# relay_power_board.net
KiCad netlist of a schematic drawn in EAGLE
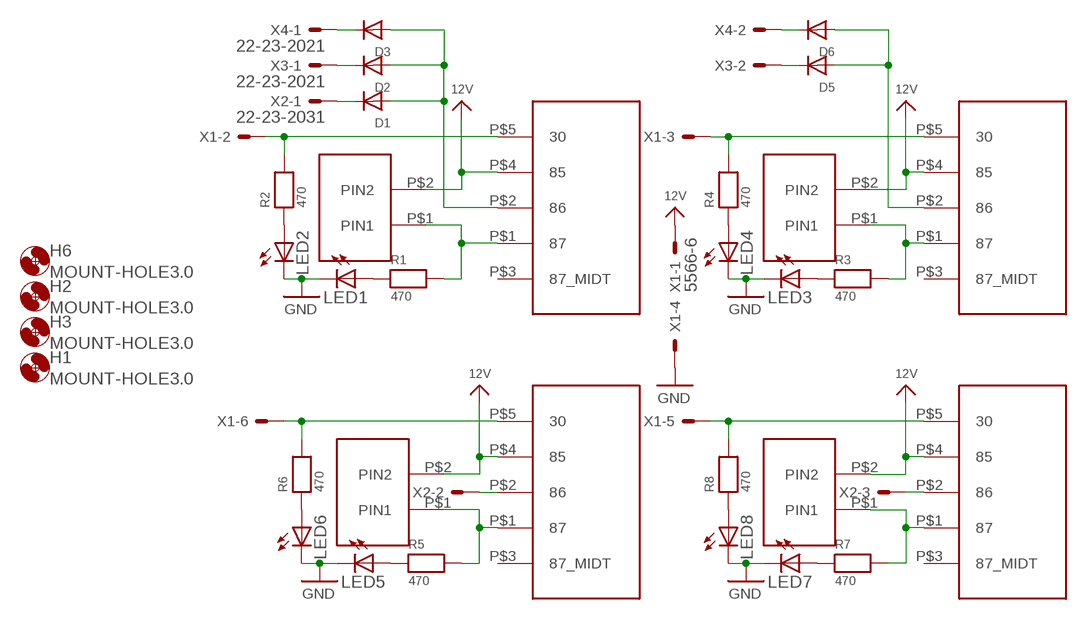
[diagram p0: schematic, sheet 1]

(export (version "E")
  (design (tool "Eeschema 10.0.6"))
  (components
    (comp (ref "D1")
      (value "DIODESMA")
      (footprint "eagle-import:SMADIODE")
      (libsource (lib "eagle-import") (part "DIODESMA"))
    )
    (comp (ref "D2")
      (value "DIODESMA")
      (footprint "eagle-import:SMADIODE")
      (libsource (lib "eagle-import") (part "DIODESMA"))
    )
    (comp (ref "D3")
      (value "DIODESMA")
      (footprint "eagle-import:SMADIODE")
      (libsource (lib "eagle-import") (part "DIODESMA"))
    )
    (comp (ref "D5")
      (value "DIODESMA")
      (footprint "eagle-import:SMADIODE")
      (libsource (lib "eagle-import") (part "DIODESMA"))
    )
    (comp (ref "D6")
      (value "DIODESMA")
      (footprint "eagle-import:SMADIODE")
      (libsource (lib "eagle-import") (part "DIODESMA"))
    )
    (comp (ref "H1")
      (value "MOUNT-HOLE3.0")
      (footprint "eagle-import:3,0")
      (libsource (lib "eagle-import") (part "MOUNT-HOLE3.0"))
    )
    (comp (ref "H2")
      (value "MOUNT-HOLE3.0")
      (footprint "eagle-import:3,0")
      (libsource (lib "eagle-import") (part "MOUNT-HOLE3.0"))
    )
    (comp (ref "H3")
      (value "MOUNT-HOLE3.0")
      (footprint "eagle-import:3,0")
      (libsource (lib "eagle-import") (part "MOUNT-HOLE3.0"))
    )
    (comp (ref "H6")
      (value "MOUNT-HOLE3.0")
      (footprint "eagle-import:3,0")
      (libsource (lib "eagle-import") (part "MOUNT-HOLE3.0"))
    )
    (comp (ref "LED1")
      (value "LEDCHIPLED_1206")
      (footprint "eagle-import:CHIPLED_1206")
      (libsource (lib "eagle-import") (part "LEDCHIPLED_1206"))
    )
    (comp (ref "LED2")
      (value "LEDCHIPLED_1206")
      (footprint "eagle-import:CHIPLED_1206")
      (libsource (lib "eagle-import") (part "LEDCHIPLED_1206"))
    )
    (comp (ref "LED3")
      (value "LEDCHIPLED_1206")
      (footprint "eagle-import:CHIPLED_1206")
      (libsource (lib "eagle-import") (part "LEDCHIPLED_1206"))
    )
    (comp (ref "LED4")
      (value "LEDCHIPLED_1206")
      (footprint "eagle-import:CHIPLED_1206")
      (libsource (lib "eagle-import") (part "LEDCHIPLED_1206"))
    )
    (comp (ref "LED5")
      (value "LEDCHIPLED_1206")
      (footprint "eagle-import:CHIPLED_1206")
      (libsource (lib "eagle-import") (part "LEDCHIPLED_1206"))
    )
    (comp (ref "LED6")
      (value "LEDCHIPLED_1206")
      (footprint "eagle-import:CHIPLED_1206")
      (libsource (lib "eagle-import") (part "LEDCHIPLED_1206"))
    )
    (comp (ref "LED7")
      (value "LEDCHIPLED_1206")
      (footprint "eagle-import:CHIPLED_1206")
      (libsource (lib "eagle-import") (part "LEDCHIPLED_1206"))
    )
    (comp (ref "LED8")
      (value "LEDCHIPLED_1206")
      (footprint "eagle-import:CHIPLED_1206")
      (libsource (lib "eagle-import") (part "LEDCHIPLED_1206"))
    )
    (comp (ref "R1")
      (value "470")
      (footprint "eagle-import:_0603")
      (libsource (lib "eagle-import") (part "RESISTOR_0603"))
    )
    (comp (ref "R2")
      (value "470")
      (footprint "eagle-import:_0603")
      (libsource (lib "eagle-import") (part "RESISTOR_0603"))
    )
    (comp (ref "R3")
      (value "470")
      (footprint "eagle-import:_0603")
      (libsource (lib "eagle-import") (part "RESISTOR_0603"))
    )
    (comp (ref "R4")
      (value "470")
      (footprint "eagle-import:_0603")
      (libsource (lib "eagle-import") (part "RESISTOR_0603"))
    )
    (comp (ref "R5")
      (value "470")
      (footprint "eagle-import:_0603")
      (libsource (lib "eagle-import") (part "RESISTOR_0603"))
    )
    (comp (ref "R6")
      (value "470")
      (footprint "eagle-import:_0603")
      (libsource (lib "eagle-import") (part "RESISTOR_0603"))
    )
    (comp (ref "R7")
      (value "470")
      (footprint "eagle-import:_0603")
      (libsource (lib "eagle-import") (part "RESISTOR_0603"))
    )
    (comp (ref "R8")
      (value "470")
      (footprint "eagle-import:_0603")
      (libsource (lib "eagle-import") (part "RESISTOR_0603"))
    )
    (comp (ref "U$1")
      (value "FUSE_SOCKET")
      (footprint "eagle-import:FUSE_SOCKET_12V_30A")
      (libsource (lib "eagle-import") (part "FUSE_SOCKET"))
    )
    (comp (ref "U$2")
      (value "FUSE_SOCKET")
      (footprint "eagle-import:FUSE_SOCKET_12V_30A")
      (libsource (lib "eagle-import") (part "FUSE_SOCKET"))
    )
    (comp (ref "U$3")
      (value "LITTE_FUSE")
      (footprint "eagle-import:LITTE_FUSE_PAC")
      (libsource (lib "eagle-import") (part "LITTE_FUSE"))
    )
    (comp (ref "U$4")
      (value "FUSE_SOCKET")
      (footprint "eagle-import:FUSE_SOCKET_12V_30A")
      (libsource (lib "eagle-import") (part "FUSE_SOCKET"))
    )
    (comp (ref "U$5")
      (value "LITTE_FUSE")
      (footprint "eagle-import:LITTE_FUSE_PAC")
      (libsource (lib "eagle-import") (part "LITTE_FUSE"))
    )
    (comp (ref "U$10")
      (value "FUSE_SOCKET")
      (footprint "eagle-import:FUSE_SOCKET_12V_30A")
      (libsource (lib "eagle-import") (part "FUSE_SOCKET"))
    )
    (comp (ref "U$11")
      (value "LITTE_FUSE")
      (footprint "eagle-import:LITTE_FUSE_PAC")
      (libsource (lib "eagle-import") (part "LITTE_FUSE"))
    )
    (comp (ref "U$18")
      (value "LITTE_FUSE")
      (footprint "eagle-import:LITTE_FUSE_PAC")
      (libsource (lib "eagle-import") (part "LITTE_FUSE"))
    )
    (comp (ref "X1")
      (value "5566-6")
      (footprint "eagle-import:5566-6")
      (fields (field (name "MPN") "95566-61002"))
      (libsource (lib "eagle-import") (part "5566-6"))
    )
    (comp (ref "X2")
      (value "22-23-2031")
      (footprint "eagle-import:22-23-2031")
      (fields (field (name "MF") "MOLEX"))
      (libsource (lib "eagle-import") (part "22-23-2031"))
    )
    (comp (ref "X3")
      (value "22-23-2021")
      (footprint "eagle-import:22-23-2021")
      (fields (field (name "MF") "MOLEX"))
      (libsource (lib "eagle-import") (part "22-23-2021"))
    )
    (comp (ref "X4")
      (value "22-23-2021")
      (footprint "eagle-import:22-23-2021")
      (fields (field (name "MF") "MOLEX"))
      (libsource (lib "eagle-import") (part "22-23-2021"))
    )
  )
  (nets
    (net (code "1") (name "12V") (class "Default")
      (node (ref "U$1") (pin "P$4") (pinfunction "85_P$4") (pintype "bidirectional"))
      (node (ref "U$10") (pin "P$4") (pinfunction "85_P$4") (pintype "bidirectional"))
      (node (ref "U$11") (pin "P$2") (pinfunction "PIN2_P$2") (pintype "bidirectional"))
      (node (ref "U$18") (pin "P$2") (pinfunction "PIN2_P$2") (pintype "bidirectional"))
      (node (ref "U$2") (pin "P$4") (pinfunction "85_P$4") (pintype "bidirectional"))
      (node (ref "U$3") (pin "P$2") (pinfunction "PIN2_P$2") (pintype "bidirectional"))
      (node (ref "U$4") (pin "P$4") (pinfunction "85_P$4") (pintype "bidirectional"))
      (node (ref "U$5") (pin "P$2") (pinfunction "PIN2_P$2") (pintype "bidirectional"))
      (node (ref "X1") (pin "1") (pinfunction "S_1") (pintype "passive"))
    )
    (net (code "2") (name "GND") (class "Default")
      (node (ref "LED1") (pin "C") (pinfunction "C_C") (pintype "passive"))
      (node (ref "LED2") (pin "C") (pinfunction "C_C") (pintype "passive"))
      (node (ref "LED3") (pin "C") (pinfunction "C_C") (pintype "passive"))
      (node (ref "LED4") (pin "C") (pinfunction "C_C") (pintype "passive"))
      (node (ref "LED5") (pin "C") (pinfunction "C_C") (pintype "passive"))
      (node (ref "LED6") (pin "C") (pinfunction "C_C") (pintype "passive"))
      (node (ref "LED7") (pin "C") (pinfunction "C_C") (pintype "passive"))
      (node (ref "LED8") (pin "C") (pinfunction "C_C") (pintype "passive"))
      (node (ref "X1") (pin "4") (pinfunction "S_4") (pintype "passive"))
    )
    (net (code "3") (name "Net-(LED1-PadA)") (class "Default")
      (node (ref "LED1") (pin "A") (pinfunction "A_A") (pintype "passive"))
      (node (ref "R1") (pin "1") (pinfunction "1_1") (pintype "passive"))
    )
    (net (code "4") (name "Net-(LED2-PadA)") (class "Default")
      (node (ref "LED2") (pin "A") (pinfunction "A_A") (pintype "passive"))
      (node (ref "R2") (pin "1") (pinfunction "1_1") (pintype "passive"))
    )
    (net (code "5") (name "Net-(LED3-PadA)") (class "Default")
      (node (ref "LED3") (pin "A") (pinfunction "A_A") (pintype "passive"))
      (node (ref "R3") (pin "1") (pinfunction "1_1") (pintype "passive"))
    )
    (net (code "6") (name "Net-(LED4-PadA)") (class "Default")
      (node (ref "LED4") (pin "A") (pinfunction "A_A") (pintype "passive"))
      (node (ref "R4") (pin "1") (pinfunction "1_1") (pintype "passive"))
    )
    (net (code "7") (name "Net-(LED5-PadA)") (class "Default")
      (node (ref "LED5") (pin "A") (pinfunction "A_A") (pintype "passive"))
      (node (ref "R5") (pin "1") (pinfunction "1_1") (pintype "passive"))
    )
    (net (code "8") (name "Net-(LED6-PadA)") (class "Default")
      (node (ref "LED6") (pin "A") (pinfunction "A_A") (pintype "passive"))
      (node (ref "R6") (pin "1") (pinfunction "1_1") (pintype "passive"))
    )
    (net (code "9") (name "Net-(LED7-PadA)") (class "Default")
      (node (ref "LED7") (pin "A") (pinfunction "A_A") (pintype "passive"))
      (node (ref "R7") (pin "1") (pinfunction "1_1") (pintype "passive"))
    )
    (net (code "10") (name "Net-(LED8-PadA)") (class "Default")
      (node (ref "LED8") (pin "A") (pinfunction "A_A") (pintype "passive"))
      (node (ref "R8") (pin "1") (pinfunction "1_1") (pintype "passive"))
    )
    (net (code "11") (name "Net-(U$1-30)") (class "Default")
      (node (ref "R2") (pin "2") (pinfunction "2_2") (pintype "passive"))
      (node (ref "U$1") (pin "P$5") (pinfunction "30_P$5") (pintype "bidirectional"))
      (node (ref "X1") (pin "2") (pinfunction "S_2") (pintype "passive"))
    )
    (net (code "12") (name "Net-(U$1-86)") (class "Default")
      (node (ref "D1") (pin "A") (pinfunction "A_A") (pintype "passive"))
      (node (ref "D2") (pin "A") (pinfunction "A_A") (pintype "passive"))
      (node (ref "D3") (pin "A") (pinfunction "A_A") (pintype "passive"))
      (node (ref "U$1") (pin "P$2") (pinfunction "86_P$2") (pintype "bidirectional"))
    )
    (net (code "13") (name "Net-(U$1-87)") (class "Default")
      (node (ref "R1") (pin "2") (pinfunction "2_2") (pintype "passive"))
      (node (ref "U$1") (pin "P$1") (pinfunction "87_P$1") (pintype "bidirectional"))
      (node (ref "U$5") (pin "P$1") (pinfunction "PIN1_P$1") (pintype "bidirectional"))
    )
    (net (code "14") (name "Net-(U$2-30)") (class "Default")
      (node (ref "R4") (pin "2") (pinfunction "2_2") (pintype "passive"))
      (node (ref "U$2") (pin "P$5") (pinfunction "30_P$5") (pintype "bidirectional"))
      (node (ref "X1") (pin "3") (pinfunction "S_3") (pintype "passive"))
    )
    (net (code "15") (name "Net-(U$2-86)") (class "Default")
      (node (ref "D5") (pin "A") (pinfunction "A_A") (pintype "passive"))
      (node (ref "D6") (pin "A") (pinfunction "A_A") (pintype "passive"))
      (node (ref "U$2") (pin "P$2") (pinfunction "86_P$2") (pintype "bidirectional"))
    )
    (net (code "16") (name "Net-(U$2-87)") (class "Default")
      (node (ref "R3") (pin "2") (pinfunction "2_2") (pintype "passive"))
      (node (ref "U$2") (pin "P$1") (pinfunction "87_P$1") (pintype "bidirectional"))
      (node (ref "U$3") (pin "P$1") (pinfunction "PIN1_P$1") (pintype "bidirectional"))
    )
    (net (code "17") (name "Net-(U$4-30)") (class "Default")
      (node (ref "R8") (pin "2") (pinfunction "2_2") (pintype "passive"))
      (node (ref "U$4") (pin "P$5") (pinfunction "30_P$5") (pintype "bidirectional"))
      (node (ref "X1") (pin "5") (pinfunction "S_5") (pintype "passive"))
    )
    (net (code "18") (name "Net-(U$4-86)") (class "Default")
      (node (ref "U$4") (pin "P$2") (pinfunction "86_P$2") (pintype "bidirectional"))
      (node (ref "X2") (pin "3") (pinfunction "S_3") (pintype "passive"))
    )
    (net (code "19") (name "Net-(U$10-30)") (class "Default")
      (node (ref "R6") (pin "2") (pinfunction "2_2") (pintype "passive"))
      (node (ref "U$10") (pin "P$5") (pinfunction "30_P$5") (pintype "bidirectional"))
      (node (ref "X1") (pin "6") (pinfunction "S_6") (pintype "passive"))
    )
    (net (code "20") (name "Net-(U$10-86)") (class "Default")
      (node (ref "U$10") (pin "P$2") (pinfunction "86_P$2") (pintype "bidirectional"))
      (node (ref "X2") (pin "2") (pinfunction "S_2") (pintype "passive"))
    )
    (net (code "21") (name "Net-(U$10-87)") (class "Default")
      (node (ref "R5") (pin "2") (pinfunction "2_2") (pintype "passive"))
      (node (ref "U$10") (pin "P$1") (pinfunction "87_P$1") (pintype "bidirectional"))
      (node (ref "U$11") (pin "P$1") (pinfunction "PIN1_P$1") (pintype "bidirectional"))
    )
    (net (code "22") (name "Net-(U$18-PIN1)") (class "Default")
      (node (ref "R7") (pin "2") (pinfunction "2_2") (pintype "passive"))
      (node (ref "U$18") (pin "P$1") (pinfunction "PIN1_P$1") (pintype "bidirectional"))
      (node (ref "U$4") (pin "P$1") (pinfunction "87_P$1") (pintype "bidirectional"))
    )
    (net (code "23") (name "Net-(X2A-S)") (class "Default")
      (node (ref "D1") (pin "C") (pinfunction "C_C") (pintype "passive"))
      (node (ref "X2") (pin "1") (pinfunction "S_1") (pintype "passive"))
    )
    (net (code "24") (name "Net-(X3A-S)") (class "Default")
      (node (ref "D2") (pin "C") (pinfunction "C_C") (pintype "passive"))
      (node (ref "X3") (pin "1") (pinfunction "S_1") (pintype "passive"))
    )
    (net (code "25") (name "Net-(X3B-S)") (class "Default")
      (node (ref "D5") (pin "C") (pinfunction "C_C") (pintype "passive"))
      (node (ref "X3") (pin "2") (pinfunction "S_2") (pintype "passive"))
    )
    (net (code "26") (name "Net-(X4A-S)") (class "Default")
      (node (ref "D3") (pin "C") (pinfunction "C_C") (pintype "passive"))
      (node (ref "X4") (pin "1") (pinfunction "S_1") (pintype "passive"))
    )
    (net (code "27") (name "Net-(X4B-S)") (class "Default")
      (node (ref "D6") (pin "C") (pinfunction "C_C") (pintype "passive"))
      (node (ref "X4") (pin "2") (pinfunction "S_2") (pintype "passive"))
    )
    (net (code "28") (name "unconnected-(U$1-87_MIDT-PadP$3)") (class "Default")
      (node (ref "U$1") (pin "P$3") (pinfunction "87_MIDT_P$3") (pintype "bidirectional"))
    )
    (net (code "29") (name "unconnected-(U$2-87_MIDT-PadP$3)") (class "Default")
      (node (ref "U$2") (pin "P$3") (pinfunction "87_MIDT_P$3") (pintype "bidirectional"))
    )
    (net (code "30") (name "unconnected-(U$4-87_MIDT-PadP$3)") (class "Default")
      (node (ref "U$4") (pin "P$3") (pinfunction "87_MIDT_P$3") (pintype "bidirectional"))
    )
    (net (code "31") (name "unconnected-(U$10-87_MIDT-PadP$3)") (class "Default")
      (node (ref "U$10") (pin "P$3") (pinfunction "87_MIDT_P$3") (pintype "bidirectional"))
    )
  )
)
